# the-why.net
KiCad netlist of a schematic drawn in EAGLE
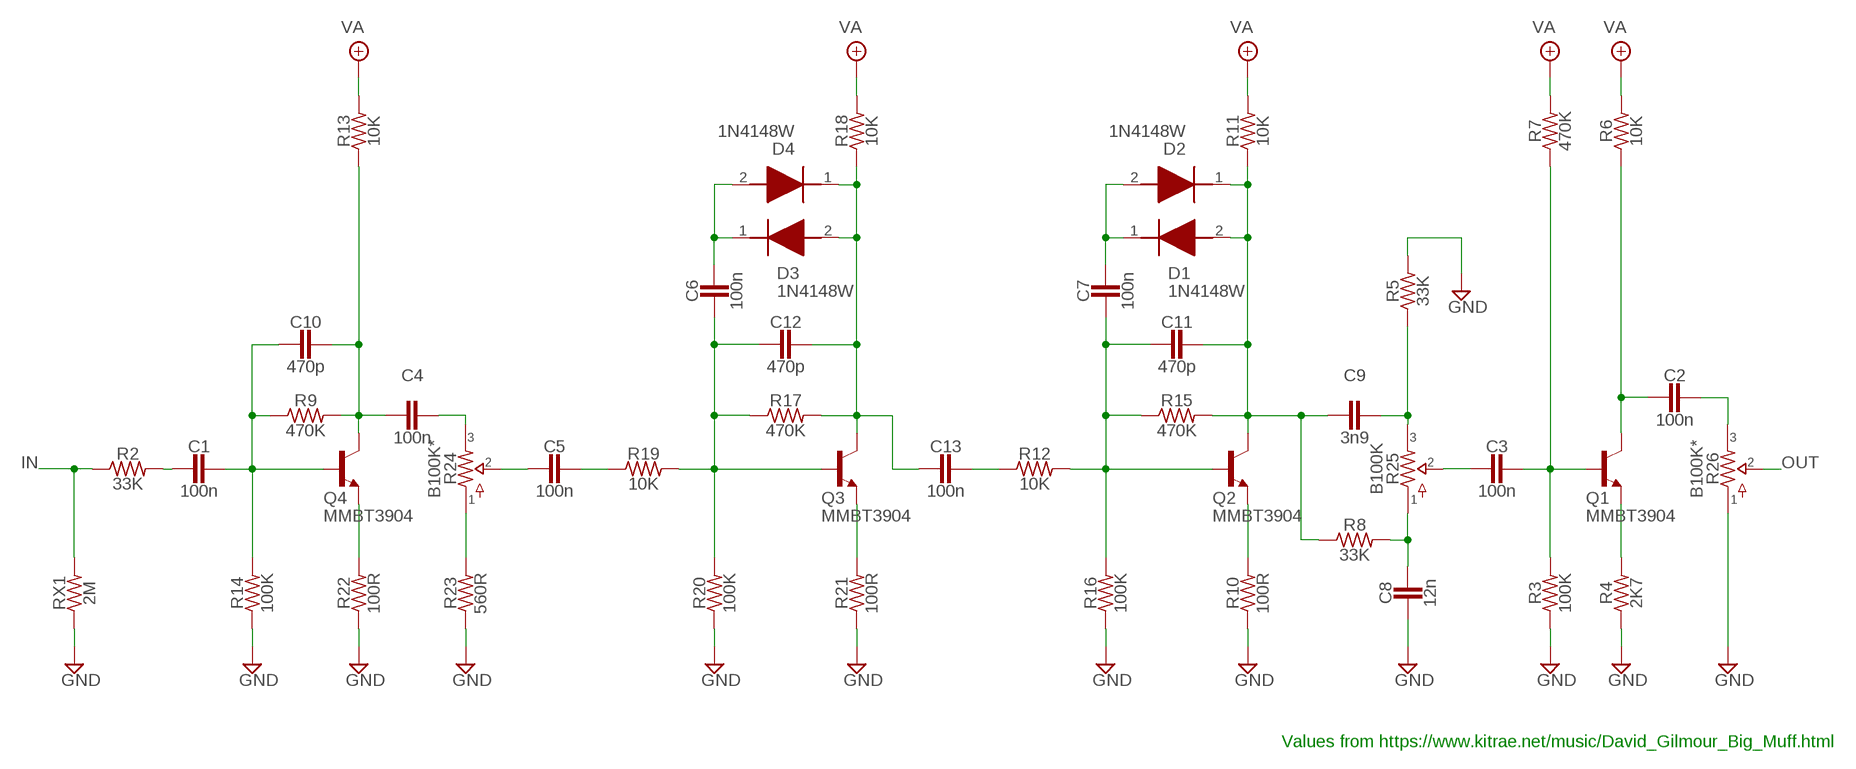
[diagram p0: schematic, sheet 1]
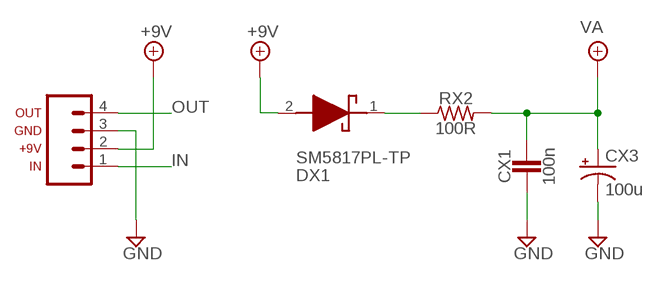
[diagram p1: schematic, sheet 2]

(export (version "E")
  (design (tool "Eeschema 10.0.6"))
  (components
    (comp (ref "C1")
      (value "100n")
      (footprint "eagle-import:RESISTOR_C1206")
      (libsource (lib "eagle-import") (part "CAP1206"))
    )
    (comp (ref "C2")
      (value "100n")
      (footprint "eagle-import:RESISTOR_C1206")
      (libsource (lib "eagle-import") (part "CAP1206"))
    )
    (comp (ref "C3")
      (value "100n")
      (footprint "eagle-import:RESISTOR_C1206")
      (libsource (lib "eagle-import") (part "CAP1206"))
    )
    (comp (ref "C4")
      (value "100n")
      (footprint "eagle-import:RESISTOR_C1206")
      (libsource (lib "eagle-import") (part "CAP1206"))
    )
    (comp (ref "C5")
      (value "100n")
      (footprint "eagle-import:RESISTOR_C1206")
      (libsource (lib "eagle-import") (part "CAP1206"))
    )
    (comp (ref "C6")
      (value "100n")
      (footprint "eagle-import:RESISTOR_C1206")
      (libsource (lib "eagle-import") (part "CAP1206"))
    )
    (comp (ref "C7")
      (value "100n")
      (footprint "eagle-import:RESISTOR_C1206")
      (libsource (lib "eagle-import") (part "CAP1206"))
    )
    (comp (ref "C8")
      (value "12n")
      (footprint "eagle-import:RESISTOR_R0603")
      (libsource (lib "eagle-import") (part "CAP0603"))
    )
    (comp (ref "C9")
      (value "3n9")
      (footprint "eagle-import:RESISTOR_C1206")
      (libsource (lib "eagle-import") (part "CAP1206"))
    )
    (comp (ref "C10")
      (value "470p")
      (footprint "eagle-import:RESISTOR_R0603")
      (libsource (lib "eagle-import") (part "CAP0603"))
    )
    (comp (ref "C11")
      (value "470p")
      (footprint "eagle-import:RESISTOR_R0603")
      (libsource (lib "eagle-import") (part "CAP0603"))
    )
    (comp (ref "C12")
      (value "470p")
      (footprint "eagle-import:RESISTOR_R0603")
      (libsource (lib "eagle-import") (part "CAP0603"))
    )
    (comp (ref "C13")
      (value "100n")
      (footprint "eagle-import:RESISTOR_C1206")
      (libsource (lib "eagle-import") (part "CAP1206"))
    )
    (comp (ref "D1")
      (value "1N4148W")
      (footprint "eagle-import:SODFL3816X120N")
      (fields (field (name "MOUSER_PART_NUMBER") "637-1N4148W"))
      (libsource (lib "eagle-import") (part "1N4148W"))
    )
    (comp (ref "D2")
      (value "1N4148W")
      (footprint "eagle-import:SODFL3816X120N")
      (fields (field (name "MOUSER_PART_NUMBER") "637-1N4148W"))
      (libsource (lib "eagle-import") (part "1N4148W"))
    )
    (comp (ref "D3")
      (value "1N4148W")
      (footprint "eagle-import:SODFL3816X120N")
      (fields (field (name "MOUSER_PART_NUMBER") "637-1N4148W"))
      (libsource (lib "eagle-import") (part "1N4148W"))
    )
    (comp (ref "D4")
      (value "1N4148W")
      (footprint "eagle-import:SODFL3816X120N")
      (fields (field (name "MOUSER_PART_NUMBER") "637-1N4148W"))
      (libsource (lib "eagle-import") (part "1N4148W"))
    )
    (comp (ref "Q1")
      (value "MMBT3904")
      (footprint "eagle-import:TRANSISTOR_SOT23-BEC")
      (libsource (lib "eagle-import") (part "BJTSOT23"))
    )
    (comp (ref "Q2")
      (value "MMBT3904")
      (footprint "eagle-import:TRANSISTOR_SOT23-BEC")
      (libsource (lib "eagle-import") (part "BJTSOT23"))
    )
    (comp (ref "Q3")
      (value "MMBT3904")
      (footprint "eagle-import:TRANSISTOR_SOT23-BEC")
      (libsource (lib "eagle-import") (part "BJTSOT23"))
    )
    (comp (ref "Q4")
      (value "MMBT3904")
      (footprint "eagle-import:TRANSISTOR_SOT23-BEC")
      (libsource (lib "eagle-import") (part "BJTSOT23"))
    )
    (comp (ref "R2")
      (value "33K")
      (footprint "eagle-import:RESISTOR_R0603")
      (libsource (lib "eagle-import") (part "RESISTOR0603"))
    )
    (comp (ref "R3")
      (value "100K")
      (footprint "eagle-import:RESISTOR_R0603")
      (libsource (lib "eagle-import") (part "RESISTOR0603"))
    )
    (comp (ref "R4")
      (value "2K7")
      (footprint "eagle-import:RESISTOR_R0603")
      (libsource (lib "eagle-import") (part "RESISTOR0603"))
    )
    (comp (ref "R5")
      (value "33K")
      (footprint "eagle-import:RESISTOR_R0603")
      (libsource (lib "eagle-import") (part "RESISTOR0603"))
    )
    (comp (ref "R6")
      (value "10K")
      (footprint "eagle-import:RESISTOR_R0603")
      (libsource (lib "eagle-import") (part "RESISTOR0603"))
    )
    (comp (ref "R7")
      (value "470K")
      (footprint "eagle-import:RESISTOR_R0603")
      (libsource (lib "eagle-import") (part "RESISTOR0603"))
    )
    (comp (ref "R8")
      (value "33K")
      (footprint "eagle-import:RESISTOR_R0603")
      (libsource (lib "eagle-import") (part "RESISTOR0603"))
    )
    (comp (ref "R9")
      (value "470K")
      (footprint "eagle-import:RESISTOR_R0603")
      (libsource (lib "eagle-import") (part "RESISTOR0603"))
    )
    (comp (ref "R10")
      (value "100R")
      (footprint "eagle-import:RESISTOR_R0603")
      (libsource (lib "eagle-import") (part "RESISTOR0603"))
    )
    (comp (ref "R11")
      (value "10K")
      (footprint "eagle-import:RESISTOR_R0603")
      (libsource (lib "eagle-import") (part "RESISTOR0603"))
    )
    (comp (ref "R12")
      (value "10K")
      (footprint "eagle-import:RESISTOR_R0603")
      (libsource (lib "eagle-import") (part "RESISTOR0603"))
    )
    (comp (ref "R13")
      (value "10K")
      (footprint "eagle-import:RESISTOR_R0603")
      (libsource (lib "eagle-import") (part "RESISTOR0603"))
    )
    (comp (ref "R14")
      (value "100K")
      (footprint "eagle-import:RESISTOR_R0603")
      (libsource (lib "eagle-import") (part "RESISTOR0603"))
    )
    (comp (ref "R15")
      (value "470K")
      (footprint "eagle-import:RESISTOR_R0603")
      (libsource (lib "eagle-import") (part "RESISTOR0603"))
    )
    (comp (ref "R16")
      (value "100K")
      (footprint "eagle-import:RESISTOR_R0603")
      (libsource (lib "eagle-import") (part "RESISTOR0603"))
    )
    (comp (ref "R17")
      (value "470K")
      (footprint "eagle-import:RESISTOR_R0603")
      (libsource (lib "eagle-import") (part "RESISTOR0603"))
    )
    (comp (ref "R18")
      (value "10K")
      (footprint "eagle-import:RESISTOR_R0603")
      (libsource (lib "eagle-import") (part "RESISTOR0603"))
    )
    (comp (ref "R19")
      (value "10K")
      (footprint "eagle-import:RESISTOR_R0603")
      (libsource (lib "eagle-import") (part "RESISTOR0603"))
    )
    (comp (ref "R20")
      (value "100K")
      (footprint "eagle-import:RESISTOR_R0603")
      (libsource (lib "eagle-import") (part "RESISTOR0603"))
    )
    (comp (ref "R21")
      (value "100R")
      (footprint "eagle-import:RESISTOR_R0603")
      (libsource (lib "eagle-import") (part "RESISTOR0603"))
    )
    (comp (ref "R22")
      (value "100R")
      (footprint "eagle-import:RESISTOR_R0603")
      (libsource (lib "eagle-import") (part "RESISTOR0603"))
    )
    (comp (ref "R23")
      (value "560R")
      (footprint "eagle-import:RESISTOR_R0603")
      (libsource (lib "eagle-import") (part "RESISTOR0603"))
    )
    (comp (ref "R24")
      (value "B100K*")
      (footprint "eagle-import:16MM_B.MOUNT")
      (libsource (lib "eagle-import") (part "16MM.1"))
    )
    (comp (ref "R25")
      (value "B100K")
      (footprint "eagle-import:16MM_B.MOUNT")
      (libsource (lib "eagle-import") (part "16MM.1"))
    )
    (comp (ref "R26")
      (value "B100K*")
      (footprint "eagle-import:16MM_B.MOUNT")
      (libsource (lib "eagle-import") (part "16MM.1"))
    )
    (comp (ref "RX1")
      (value "2M")
      (footprint "eagle-import:RESISTOR_R0603")
      (libsource (lib "eagle-import") (part "RESISTOR0603"))
    )
    (comp (ref "CX1")
      (value "100n")
      (footprint "eagle-import:RESISTOR_R0603")
      (libsource (lib "eagle-import") (part "CAP0603"))
    )
    (comp (ref "CX3")
      (value "100u")
      (footprint "eagle-import:063_025")
      (libsource (lib "eagle-import") (part "0631"))
    )
    (comp (ref "DX1")
      (value "SM5817PL-TP")
      (footprint "eagle-import:SOD3716X120N")
      (fields (field (name "MOUSER_PART_NUMBER") "833-SM5817PL-TP"))
      (libsource (lib "eagle-import") (part "SM5817PL-TP"))
    )
    (comp (ref "J101")
      (value "1X04_SMD_STRAIGHT_COMBO")
      (footprint "eagle-import:1X04")
      (libsource (lib "eagle-import") (part "CONN_04PTH"))
    )
    (comp (ref "RX2")
      (value "100R")
      (footprint "eagle-import:RESISTOR_R0603")
      (libsource (lib "eagle-import") (part "RESISTOR0603"))
    )
  )
  (nets
    (net (code "1") (name "+9V") (class "Default")
      (node (ref "DX1") (pin "2") (pinfunction "A_2") (pintype "bidirectional"))
      (node (ref "J101") (pin "2") (pinfunction "+9V_2") (pintype "passive"))
    )
    (net (code "2") (name "GND") (class "Default")
      (node (ref "C8") (pin "2") (pinfunction "2_2") (pintype "passive"))
      (node (ref "CX1") (pin "2") (pinfunction "2_2") (pintype "passive"))
      (node (ref "CX3") (pin "-") (pinfunction "-_-") (pintype "passive"))
      (node (ref "J101") (pin "3") (pinfunction "GND_3") (pintype "passive"))
      (node (ref "R10") (pin "1") (pinfunction "1_1") (pintype "passive"))
      (node (ref "R14") (pin "1") (pinfunction "1_1") (pintype "passive"))
      (node (ref "R16") (pin "1") (pinfunction "1_1") (pintype "passive"))
      (node (ref "R20") (pin "1") (pinfunction "1_1") (pintype "passive"))
      (node (ref "R21") (pin "1") (pinfunction "1_1") (pintype "passive"))
      (node (ref "R22") (pin "1") (pinfunction "1_1") (pintype "passive"))
      (node (ref "R23") (pin "1") (pinfunction "1_1") (pintype "passive"))
      (node (ref "R26") (pin "1") (pinfunction "1_1") (pintype "passive"))
      (node (ref "R3") (pin "1") (pinfunction "1_1") (pintype "passive"))
      (node (ref "R4") (pin "1") (pinfunction "1_1") (pintype "passive"))
      (node (ref "R5") (pin "2") (pinfunction "2_2") (pintype "passive"))
      (node (ref "RX1") (pin "1") (pinfunction "1_1") (pintype "passive"))
    )
    (net (code "3") (name "IN") (class "Default")
      (node (ref "J101") (pin "1") (pinfunction "IN_1") (pintype "passive"))
      (node (ref "R2") (pin "1") (pinfunction "1_1") (pintype "passive"))
      (node (ref "RX1") (pin "2") (pinfunction "2_2") (pintype "passive"))
    )
    (net (code "4") (name "Net-(C1-Pad1)") (class "Default")
      (node (ref "C1") (pin "1") (pinfunction "1_1") (pintype "passive"))
      (node (ref "C10") (pin "2") (pinfunction "2_2") (pintype "passive"))
      (node (ref "Q4") (pin "B") (pinfunction "B_B") (pintype "passive"))
      (node (ref "R14") (pin "2") (pinfunction "2_2") (pintype "passive"))
      (node (ref "R9") (pin "1") (pinfunction "1_1") (pintype "passive"))
    )
    (net (code "5") (name "Net-(C1-Pad2)") (class "Default")
      (node (ref "C1") (pin "2") (pinfunction "2_2") (pintype "passive"))
      (node (ref "R2") (pin "2") (pinfunction "2_2") (pintype "passive"))
    )
    (net (code "6") (name "Net-(C2-Pad1)") (class "Default")
      (node (ref "C2") (pin "1") (pinfunction "1_1") (pintype "passive"))
      (node (ref "R26") (pin "3") (pinfunction "3_3") (pintype "passive"))
    )
    (net (code "7") (name "Net-(C2-Pad2)") (class "Default")
      (node (ref "C2") (pin "2") (pinfunction "2_2") (pintype "passive"))
      (node (ref "Q1") (pin "C") (pinfunction "C_C") (pintype "passive"))
      (node (ref "R6") (pin "1") (pinfunction "1_1") (pintype "passive"))
    )
    (net (code "8") (name "Net-(C3-Pad1)") (class "Default")
      (node (ref "C3") (pin "1") (pinfunction "1_1") (pintype "passive"))
      (node (ref "Q1") (pin "B") (pinfunction "B_B") (pintype "passive"))
      (node (ref "R3") (pin "2") (pinfunction "2_2") (pintype "passive"))
      (node (ref "R7") (pin "1") (pinfunction "1_1") (pintype "passive"))
    )
    (net (code "9") (name "Net-(C3-Pad2)") (class "Default")
      (node (ref "C3") (pin "2") (pinfunction "2_2") (pintype "passive"))
      (node (ref "R25") (pin "2") (pinfunction "2_2") (pintype "passive"))
    )
    (net (code "10") (name "Net-(C4-Pad1)") (class "Default")
      (node (ref "C4") (pin "1") (pinfunction "1_1") (pintype "passive"))
      (node (ref "R24") (pin "3") (pinfunction "3_3") (pintype "passive"))
    )
    (net (code "11") (name "Net-(C5-Pad1)") (class "Default")
      (node (ref "C5") (pin "1") (pinfunction "1_1") (pintype "passive"))
      (node (ref "R19") (pin "1") (pinfunction "1_1") (pintype "passive"))
    )
    (net (code "12") (name "Net-(C5-Pad2)") (class "Default")
      (node (ref "C5") (pin "2") (pinfunction "2_2") (pintype "passive"))
      (node (ref "R24") (pin "2") (pinfunction "2_2") (pintype "passive"))
    )
    (net (code "13") (name "Net-(C8-Pad1)") (class "Default")
      (node (ref "C8") (pin "1") (pinfunction "1_1") (pintype "passive"))
      (node (ref "R25") (pin "1") (pinfunction "1_1") (pintype "passive"))
      (node (ref "R8") (pin "2") (pinfunction "2_2") (pintype "passive"))
    )
    (net (code "14") (name "Net-(C9-Pad1)") (class "Default")
      (node (ref "C9") (pin "1") (pinfunction "1_1") (pintype "passive"))
      (node (ref "R25") (pin "3") (pinfunction "3_3") (pintype "passive"))
      (node (ref "R5") (pin "1") (pinfunction "1_1") (pintype "passive"))
    )
    (net (code "15") (name "Net-(C10-Pad1)") (class "Default")
      (node (ref "C10") (pin "1") (pinfunction "1_1") (pintype "passive"))
      (node (ref "C4") (pin "2") (pinfunction "2_2") (pintype "passive"))
      (node (ref "Q4") (pin "C") (pinfunction "C_C") (pintype "passive"))
      (node (ref "R13") (pin "1") (pinfunction "1_1") (pintype "passive"))
      (node (ref "R9") (pin "2") (pinfunction "2_2") (pintype "passive"))
    )
    (net (code "16") (name "Net-(C11-Pad2)") (class "Default")
      (node (ref "C11") (pin "2") (pinfunction "2_2") (pintype "passive"))
      (node (ref "C7") (pin "2") (pinfunction "2_2") (pintype "passive"))
      (node (ref "Q2") (pin "B") (pinfunction "B_B") (pintype "passive"))
      (node (ref "R12") (pin "2") (pinfunction "2_2") (pintype "passive"))
      (node (ref "R15") (pin "1") (pinfunction "1_1") (pintype "passive"))
      (node (ref "R16") (pin "2") (pinfunction "2_2") (pintype "passive"))
    )
    (net (code "17") (name "Net-(C12-Pad2)") (class "Default")
      (node (ref "C12") (pin "2") (pinfunction "2_2") (pintype "passive"))
      (node (ref "C6") (pin "2") (pinfunction "2_2") (pintype "passive"))
      (node (ref "Q3") (pin "B") (pinfunction "B_B") (pintype "passive"))
      (node (ref "R17") (pin "1") (pinfunction "1_1") (pintype "passive"))
      (node (ref "R19") (pin "2") (pinfunction "2_2") (pintype "passive"))
      (node (ref "R20") (pin "2") (pinfunction "2_2") (pintype "passive"))
    )
    (net (code "18") (name "Net-(C13-Pad1)") (class "Default")
      (node (ref "C13") (pin "1") (pinfunction "1_1") (pintype "passive"))
      (node (ref "R12") (pin "1") (pinfunction "1_1") (pintype "passive"))
    )
    (net (code "19") (name "Net-(D1-A)") (class "Default")
      (node (ref "C11") (pin "1") (pinfunction "1_1") (pintype "passive"))
      (node (ref "C9") (pin "2") (pinfunction "2_2") (pintype "passive"))
      (node (ref "D1") (pin "2") (pinfunction "A_2") (pintype "bidirectional"))
      (node (ref "D2") (pin "1") (pinfunction "K_1") (pintype "bidirectional"))
      (node (ref "Q2") (pin "C") (pinfunction "C_C") (pintype "passive"))
      (node (ref "R11") (pin "1") (pinfunction "1_1") (pintype "passive"))
      (node (ref "R15") (pin "2") (pinfunction "2_2") (pintype "passive"))
      (node (ref "R8") (pin "1") (pinfunction "1_1") (pintype "passive"))
    )
    (net (code "20") (name "Net-(D1-K)") (class "Default")
      (node (ref "C7") (pin "1") (pinfunction "1_1") (pintype "passive"))
      (node (ref "D1") (pin "1") (pinfunction "K_1") (pintype "bidirectional"))
      (node (ref "D2") (pin "2") (pinfunction "A_2") (pintype "bidirectional"))
    )
    (net (code "21") (name "Net-(D3-A)") (class "Default")
      (node (ref "C12") (pin "1") (pinfunction "1_1") (pintype "passive"))
      (node (ref "C13") (pin "2") (pinfunction "2_2") (pintype "passive"))
      (node (ref "D3") (pin "2") (pinfunction "A_2") (pintype "bidirectional"))
      (node (ref "D4") (pin "1") (pinfunction "K_1") (pintype "bidirectional"))
      (node (ref "Q3") (pin "C") (pinfunction "C_C") (pintype "passive"))
      (node (ref "R17") (pin "2") (pinfunction "2_2") (pintype "passive"))
      (node (ref "R18") (pin "1") (pinfunction "1_1") (pintype "passive"))
    )
    (net (code "22") (name "Net-(D3-K)") (class "Default")
      (node (ref "C6") (pin "1") (pinfunction "1_1") (pintype "passive"))
      (node (ref "D3") (pin "1") (pinfunction "K_1") (pintype "bidirectional"))
      (node (ref "D4") (pin "2") (pinfunction "A_2") (pintype "bidirectional"))
    )
    (net (code "23") (name "Net-(DX1-K)") (class "Default")
      (node (ref "DX1") (pin "1") (pinfunction "K_1") (pintype "bidirectional"))
      (node (ref "RX2") (pin "1") (pinfunction "1_1") (pintype "passive"))
    )
    (net (code "24") (name "Net-(Q1-PadE)") (class "Default")
      (node (ref "Q1") (pin "E") (pinfunction "E_E") (pintype "passive"))
      (node (ref "R4") (pin "2") (pinfunction "2_2") (pintype "passive"))
    )
    (net (code "25") (name "Net-(Q2-PadE)") (class "Default")
      (node (ref "Q2") (pin "E") (pinfunction "E_E") (pintype "passive"))
      (node (ref "R10") (pin "2") (pinfunction "2_2") (pintype "passive"))
    )
    (net (code "26") (name "Net-(Q3-PadE)") (class "Default")
      (node (ref "Q3") (pin "E") (pinfunction "E_E") (pintype "passive"))
      (node (ref "R21") (pin "2") (pinfunction "2_2") (pintype "passive"))
    )
    (net (code "27") (name "Net-(Q4-PadE)") (class "Default")
      (node (ref "Q4") (pin "E") (pinfunction "E_E") (pintype "passive"))
      (node (ref "R22") (pin "2") (pinfunction "2_2") (pintype "passive"))
    )
    (net (code "28") (name "Net-(R23-Pad2)") (class "Default")
      (node (ref "R23") (pin "2") (pinfunction "2_2") (pintype "passive"))
      (node (ref "R24") (pin "1") (pinfunction "1_1") (pintype "passive"))
    )
    (net (code "29") (name "OUT") (class "Default")
      (node (ref "J101") (pin "4") (pinfunction "OUT_4") (pintype "passive"))
      (node (ref "R26") (pin "2") (pinfunction "2_2") (pintype "passive"))
    )
    (net (code "30") (name "VA") (class "Default")
      (node (ref "CX1") (pin "1") (pinfunction "1_1") (pintype "passive"))
      (node (ref "CX3") (pin "+") (pinfunction "+_+") (pintype "passive"))
      (node (ref "R11") (pin "2") (pinfunction "2_2") (pintype "passive"))
      (node (ref "R13") (pin "2") (pinfunction "2_2") (pintype "passive"))
      (node (ref "R18") (pin "2") (pinfunction "2_2") (pintype "passive"))
      (node (ref "R6") (pin "2") (pinfunction "2_2") (pintype "passive"))
      (node (ref "R7") (pin "2") (pinfunction "2_2") (pintype "passive"))
      (node (ref "RX2") (pin "2") (pinfunction "2_2") (pintype "passive"))
    )
  )
)
